# Half_bridge_load.net
KiCad netlist of a schematic drawn in Altium Designer
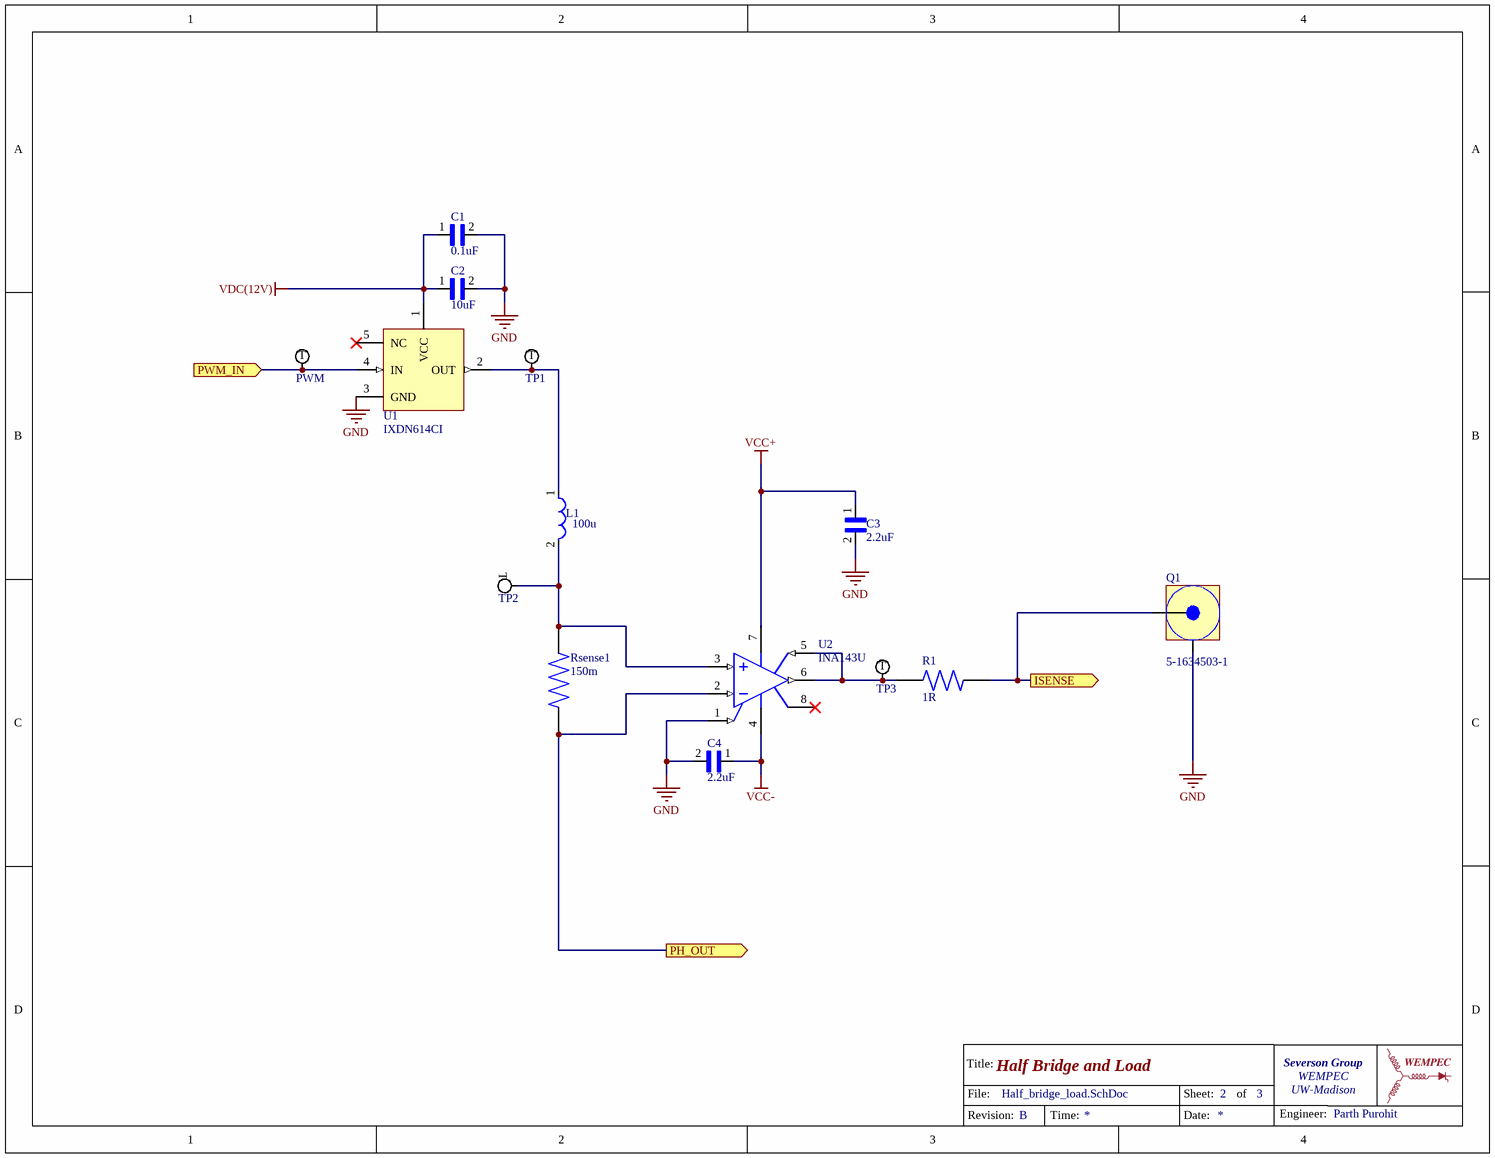
[diagram p0: Half_bridge_load.SchDoc]

(export (version "E")
  (design (tool "Eeschema 10.0.6"))
  (components
    (comp (ref "C1")
      (value "0.1uF")
      (footprint "PcbLib_uInverter:0805_CAP")
      (description "Cap Ceramic 0.1uF 35V X7R 10% SMD 0805")
      (fields
        (field (name "MANUFACTURER") "KEMET")
        (field (name "MANUFACTURER PART NUMBER") "C0805C104K6RACTU")
      )
      (libsource (lib "Schlib_uInverter") (part "C0805C104K6RACTU"))
    )
    (comp (ref "C2")
      (value "10uF")
      (footprint "PcbLib_uInverter:0805_CAP")
      (description "0805 35 V 10 uF ±10% Tolerance X5R Multilayer Ceramic Capacitor")
      (fields
        (field (name "MANUFACTURER") "Murata")
        (field (name "MANUFACTURER PART NUMBER") "GRM21BR6YA106KE43L")
      )
      (libsource (lib "Schlib_uInverter") (part "GRM21BR6YA106KE43L"))
    )
    (comp (ref "C3")
      (value "2.2uF")
      (footprint "PcbLib_uInverter:0805_CAP")
      (description "2.2 µF ±10% 35V Ceramic Capacitor X7R 0805")
      (fields
        (field (name "MANUFACTURER") "TDK")
        (field (name "MANUFACTURER PART NUMBER") "C2012X7R1V225K125AB")
      )
      (libsource (lib "") (part "C2012X7R1V225K125AB_1"))
    )
    (comp (ref "C4")
      (value "2.2uF")
      (footprint "PcbLib_uInverter:0805_CAP")
      (description "2.2 µF ±10% 35V Ceramic Capacitor X7R 0805")
      (fields
        (field (name "MANUFACTURER") "TDK")
        (field (name "MANUFACTURER PART NUMBER") "C2012X7R1V225K125AB")
      )
      (libsource (lib "Schlib_uInverter") (part "C2012X7R1V225K125AB"))
    )
    (comp (ref "L1")
      (value "100u")
      (footprint "FP-PA4344_104NLT-MFG")
      (description "FIXED IND 100UH 5.3A 118 MOHM")
      (fields (field (name "MANUFACTURER") "Pulse") (field (name "MANUFACTURER PART NUMBER") "PA4344.104NLT"))
      (libsource (lib "Schlib_uInv01") (part "PA4344.104NLT"))
    )
    (comp (ref "PWM")
      (value "Test Point")
      (footprint "TP_1.6MM")
      (description "Conn Test Point SKT 1 POS ST Thru-Hole 1 Port")
      (fields
        (field (name "MANUFACTURER") "Keystone Electronics")
        (field (name "MANUFACTURER PART NUMBER") "5005")
      )
      (libsource (lib "Schlib_uInverter") (part "Test Point 36-5005ND"))
    )
    (comp (ref "Q1")
      (value "5-1634503-1")
      (footprint "5-1634503-1")
      (description "CONN BNC JACK STR 50 OHM PCB")
      (fields (field (name "MANUFACTURER") "TE Connectivity AMP Connectors"))
      (libsource (lib "Schlib_uInv01") (part "5-1634503-1"))
    )
    (comp (ref "R1")
      (value "1R")
      (footprint "PcbLib_uInverter:0805_RES")
      (description "Res Thick Film 0805 1 Ohm 1% 1/8W")
      (fields
        (field (name "MANUFACTURER") "Vishay Dale")
        (field (name "MANUFACTURER PART NUMBER") "CRCW08051R00FKEA")
      )
      (libsource (lib "Schlib_uInverter") (part "CRCW08051R00FKEA"))
    )
    (comp (ref "Rsense1")
      (value "150m")
      (footprint "RES_15_OHM")
      (description "Resistor; Wirewound; Res 0.15 Ohms; Pwr-Rtg 5 W; Tol 1%; Axial; Silicone; Cur-Sense")
      (fields (field (name "MANUFACTURER") "Ohmite") (field (name "MANUFACTURER PART NUMBER") "15FR150E"))
      (libsource (lib "Schlib_uInv01") (part "15FR150E"))
    )
    (comp (ref "TitleBlockWEMPEC2")
      (value "TitleBlockWEMPEC")
      (libsource (lib "Schlib_uInv01") (part "TitleBlockWEMPEC"))
    )
    (comp (ref "TP1")
      (value "Test Point")
      (footprint "TP_1.6MM")
      (description "Conn Test Point SKT 1 POS ST Thru-Hole 1 Port")
      (fields
        (field (name "MANUFACTURER") "Keystone Electronics")
        (field (name "MANUFACTURER PART NUMBER") "5005")
      )
      (libsource (lib "Schlib_uInverter") (part "Test Point 36-5005ND"))
    )
    (comp (ref "TP2")
      (value "Test Point")
      (footprint "TP_1.6MM")
      (description "Conn Test Point SKT 1 POS ST Thru-Hole 1 Port")
      (fields
        (field (name "MANUFACTURER") "Keystone Electronics")
        (field (name "MANUFACTURER PART NUMBER") "5005")
      )
      (libsource (lib "Schlib_uInverter") (part "Test Point 36-5005ND"))
    )
    (comp (ref "TP3")
      (value "Test Point")
      (footprint "TP_1.6MM")
      (description "Conn Test Point SKT 1 POS ST Thru-Hole 1 Port")
      (fields
        (field (name "MANUFACTURER") "Keystone Electronics")
        (field (name "MANUFACTURER PART NUMBER") "5005")
      )
      (libsource (lib "Schlib_uInverter") (part "Test Point 36-5005ND"))
    )
    (comp (ref "U1")
      (value "IXDN614CI")
      (footprint "IXYS_TO-220-5_IXY")
      (description "14-Ampere Low-Side Ultrafast MOSFET Driver 5-Lead TO-220")
      (fields (field (name "MANUFACTURER") "IXYS"))
      (libsource (lib "Schlib_uInv01") (part "IXDN614CI"))
    )
    (comp (ref "U2")
      (value "INA143U")
      (footprint "SOIC127P599X175-8N")
      (description "SP Amp Difference Amplifier Single ±18V/36V 8-Pin SOIC Tube")
      (fields (field (name "MANUFACTURER") "Texas Instruments"))
      (libsource (lib "Schlib_uInverter") (part "INA143U"))
    )
  )
  (nets
    (net (code "1") (name "/ISENSE") (class "Default")
      (node (ref "Q1") (pin "1") (pinfunction "1_1") (pintype "passive"))
      (node (ref "R1") (pin "2") (pinfunction "2_2") (pintype "passive"))
    )
    (net (code "2") (name "/PH_OUT") (class "Default")
      (node (ref "Rsense1") (pin "2") (pinfunction "2_2") (pintype "passive"))
      (node (ref "U2") (pin "2") (pinfunction "IN-_2") (pintype "input"))
    )
    (net (code "3") (name "/PWM_IN") (class "Default")
      (node (ref "PWM") (pin "1") (pinfunction "1_1") (pintype "passive"))
      (node (ref "U1") (pin "4") (pinfunction "IN_4") (pintype "input"))
    )
    (net (code "4") (name "GND") (class "Default")
      (node (ref "C1") (pin "2") (pinfunction "2_2") (pintype "passive"))
      (node (ref "C2") (pin "2") (pinfunction "2_2") (pintype "passive"))
      (node (ref "C3") (pin "2") (pinfunction "2_2") (pintype "passive"))
      (node (ref "C4") (pin "2") (pinfunction "2_2") (pintype "passive"))
      (node (ref "Q1") (pin "2") (pinfunction "2_2") (pintype "passive"))
      (node (ref "U1") (pin "3") (pinfunction "GND_3") (pintype "power_in"))
      (node (ref "U2") (pin "1") (pinfunction "REF_1") (pintype "input"))
    )
    (net (code "5") (name "Net-(U1-OUT)") (class "Default")
      (node (ref "L1") (pin "1") (pinfunction "1_1") (pintype "passive"))
      (node (ref "TP1") (pin "1") (pinfunction "1_1") (pintype "passive"))
      (node (ref "U1") (pin "2") (pinfunction "OUT_2") (pintype "output"))
    )
    (net (code "6") (name "Net-(U2-IN+)") (class "Default")
      (node (ref "L1") (pin "2") (pinfunction "2_2") (pintype "passive"))
      (node (ref "Rsense1") (pin "1") (pinfunction "1_1") (pintype "passive"))
      (node (ref "TP2") (pin "1") (pinfunction "1_1") (pintype "passive"))
      (node (ref "U2") (pin "3") (pinfunction "IN+_3") (pintype "input"))
    )
    (net (code "7") (name "Net-(U2-OUTPUT)") (class "Default")
      (node (ref "R1") (pin "1") (pinfunction "1_1") (pintype "passive"))
      (node (ref "TP3") (pin "1") (pinfunction "1_1") (pintype "passive"))
      (node (ref "U2") (pin "5") (pinfunction "SENSE_5") (pintype "input"))
      (node (ref "U2") (pin "6") (pinfunction "OUTPUT_6") (pintype "output"))
    )
    (net (code "8") (name "VCC+") (class "Default")
      (node (ref "C3") (pin "1") (pinfunction "1_1") (pintype "passive"))
      (node (ref "U2") (pin "7") (pinfunction "V+_7") (pintype "power_in"))
    )
    (net (code "9") (name "VCC-") (class "Default")
      (node (ref "C4") (pin "1") (pinfunction "1_1") (pintype "passive"))
      (node (ref "U2") (pin "4") (pinfunction "V-_4") (pintype "power_in"))
    )
    (net (code "10") (name "VDC(12V)") (class "Default")
      (node (ref "C1") (pin "1") (pinfunction "1_1") (pintype "passive"))
      (node (ref "C2") (pin "1") (pinfunction "1_1") (pintype "passive"))
      (node (ref "U1") (pin "1") (pinfunction "VCC_1") (pintype "power_in"))
    )
    (net (code "11") (name "unconnected-(U1-NC-Pad5)") (class "Default")
      (node (ref "U1") (pin "5") (pinfunction "NC_5") (pintype "passive+no_connect"))
    )
    (net (code "12") (name "unconnected-(U2-NC-Pad8)") (class "Default")
      (node (ref "U2") (pin "8") (pinfunction "NC_8") (pintype "passive+no_connect"))
    )
  )
)
